# design.net
KiCad netlist of a schematic drawn in Altium Designer
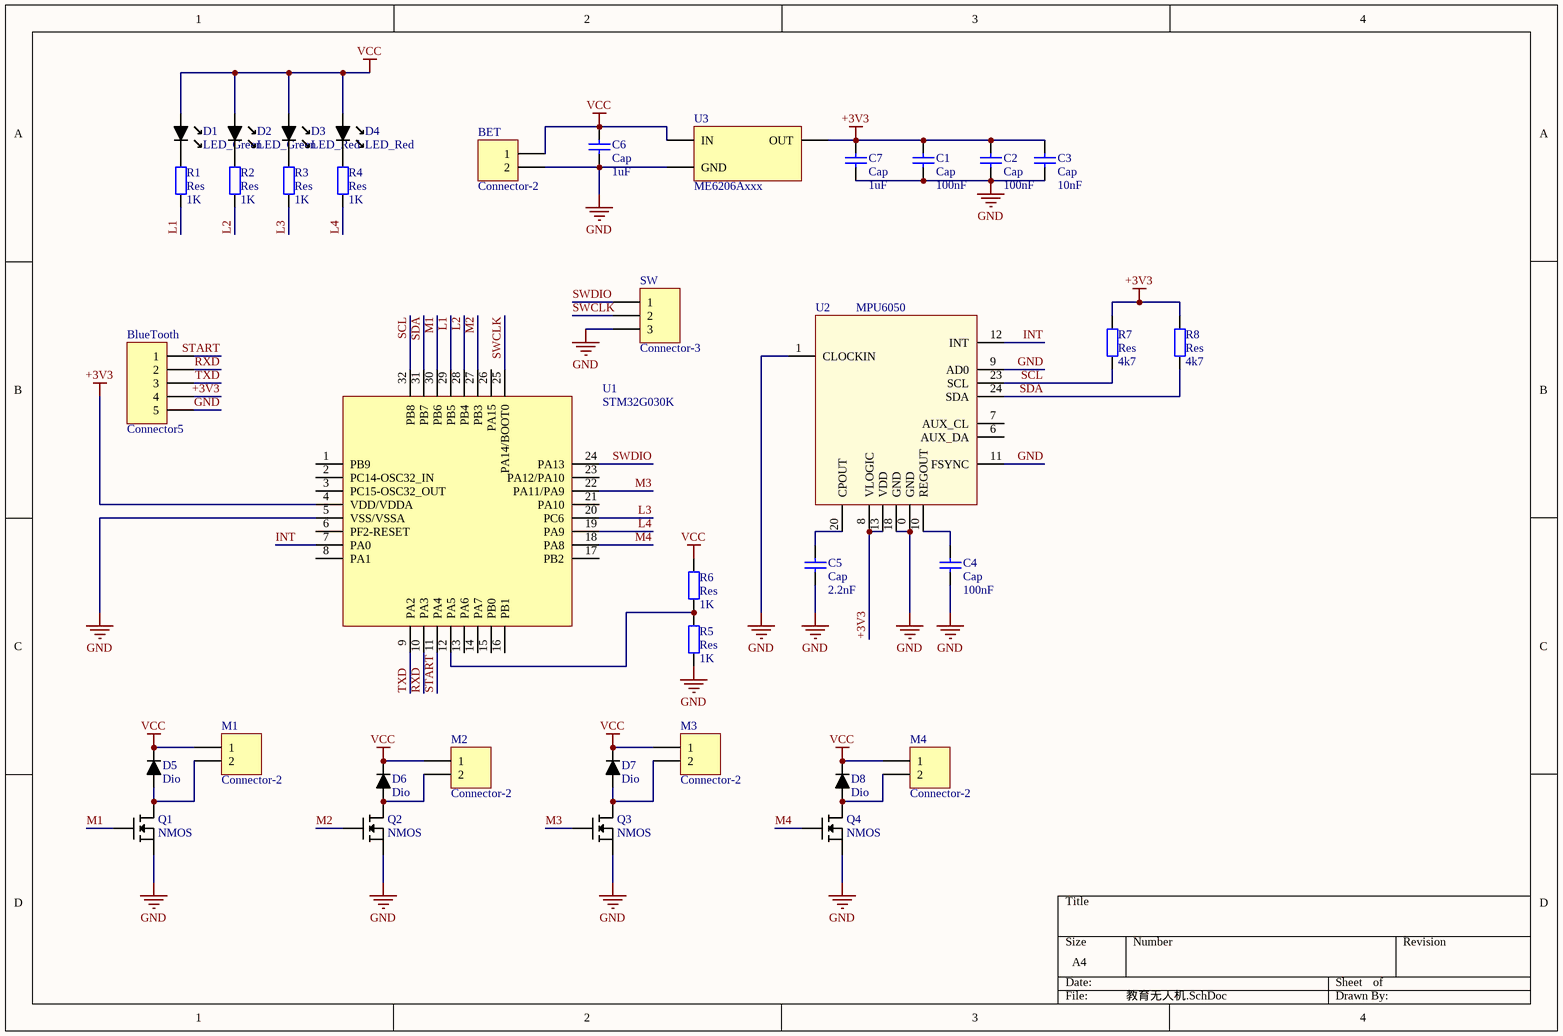
[diagram p0: 教育无人机.SchDoc]

(export (version "E")
  (design (tool "Eeschema 10.0.6"))
  (components
    (comp (ref "BET")
      (value "Connector-2")
      (footprint "XH2.54TH-2")
      (libsource (lib "") (part "Connector-2_1"))
    )
    (comp (ref "BlueTooth")
      (value "Connector5")
      (footprint "2.54th5")
      (libsource (lib "Connector") (part "Connector5"))
    )
    (comp (ref "C1")
      (value "Cap")
      (footprint "1206m")
      (description "Capacitor")
      (fields (field (name "ALTIUM_VALUE") "100nF") (field (name "PUBLISHER") "Altium Limited"))
      (libsource (lib "BasicDevice") (part "Cap"))
    )
    (comp (ref "C2")
      (value "Cap")
      (footprint "1206m")
      (description "Capacitor")
      (fields (field (name "ALTIUM_VALUE") "100nF") (field (name "PUBLISHER") "Altium Limited"))
      (libsource (lib "BasicDevice") (part "Cap"))
    )
    (comp (ref "C3")
      (value "Cap")
      (footprint "1206m")
      (description "Capacitor")
      (fields (field (name "ALTIUM_VALUE") "10nF") (field (name "PUBLISHER") "Altium Limited"))
      (libsource (lib "BasicDevice") (part "Cap"))
    )
    (comp (ref "C4")
      (value "Cap")
      (footprint "1206m")
      (description "Capacitor")
      (fields (field (name "ALTIUM_VALUE") "100nF") (field (name "PUBLISHER") "Altium Limited"))
      (libsource (lib "BasicDevice") (part "Cap"))
    )
    (comp (ref "C5")
      (value "Cap")
      (footprint "1206m")
      (description "Capacitor")
      (fields (field (name "ALTIUM_VALUE") "2.2nF") (field (name "PUBLISHER") "Altium Limited"))
      (libsource (lib "BasicDevice") (part "Cap"))
    )
    (comp (ref "C6")
      (value "Cap")
      (footprint "1206m")
      (description "Capacitor")
      (fields (field (name "ALTIUM_VALUE") "1uF") (field (name "PUBLISHER") "Altium Limited"))
      (libsource (lib "BasicDevice") (part "Cap"))
    )
    (comp (ref "C7")
      (value "Cap")
      (footprint "1206m")
      (description "Capacitor")
      (fields (field (name "ALTIUM_VALUE") "1uF") (field (name "PUBLISHER") "Altium Limited"))
      (libsource (lib "BasicDevice") (part "Cap"))
    )
    (comp (ref "D1") (value "LED_Green") (footprint "D0805M") (libsource (lib "BasicDevice") (part "LED")))
    (comp (ref "D2") (value "LED_Green") (footprint "D0805M") (libsource (lib "BasicDevice") (part "LED")))
    (comp (ref "D3") (value "LED_Red") (footprint "D0805M") (libsource (lib "BasicDevice") (part "LED")))
    (comp (ref "D4") (value "LED_Red") (footprint "D0805M") (libsource (lib "BasicDevice") (part "LED")))
    (comp (ref "D5") (value "Dio") (footprint "DO-214ACM") (libsource (lib "BasicDevice") (part "Dio")))
    (comp (ref "D6") (value "Dio") (footprint "DO-214ACM") (libsource (lib "BasicDevice") (part "Dio")))
    (comp (ref "D7") (value "Dio") (footprint "DO-214ACM") (libsource (lib "BasicDevice") (part "Dio")))
    (comp (ref "D8") (value "Dio") (footprint "DO-214ACM") (libsource (lib "BasicDevice") (part "Dio")))
    (comp (ref "M1")
      (value "Connector-2")
      (footprint "XH2.54TH-2")
      (libsource (lib "Connector") (part "Connector-2"))
    )
    (comp (ref "M2")
      (value "Connector-2")
      (footprint "XH2.54TH-2")
      (libsource (lib "Connector") (part "Connector-2"))
    )
    (comp (ref "M3")
      (value "Connector-2")
      (footprint "XH2.54TH-2")
      (libsource (lib "Connector") (part "Connector-2"))
    )
    (comp (ref "M4")
      (value "Connector-2")
      (footprint "XH2.54TH-2")
      (libsource (lib "Connector") (part "Connector-2"))
    )
    (comp (ref "Q1") (value "NMOS") (footprint "SOT23-3M") (libsource (lib "BasicDevice") (part "NMOS")))
    (comp (ref "Q2") (value "NMOS") (footprint "SOT23-3M") (libsource (lib "BasicDevice") (part "NMOS")))
    (comp (ref "Q3") (value "NMOS") (footprint "SOT23-3M") (libsource (lib "BasicDevice") (part "NMOS")))
    (comp (ref "Q4") (value "NMOS") (footprint "SOT23-3M") (libsource (lib "BasicDevice") (part "NMOS")))
    (comp (ref "R1")
      (value "Res")
      (footprint "1206M")
      (description "Resistor")
      (fields (field (name "ALTIUM_VALUE") "1K") (field (name "PUBLISHER") "Altium Limited"))
      (libsource (lib "BasicDevice") (part "Res"))
    )
    (comp (ref "R2")
      (value "Res")
      (footprint "1206M")
      (description "Resistor")
      (fields (field (name "ALTIUM_VALUE") "1K") (field (name "PUBLISHER") "Altium Limited"))
      (libsource (lib "BasicDevice") (part "Res"))
    )
    (comp (ref "R3")
      (value "Res")
      (footprint "1206M")
      (description "Resistor")
      (fields (field (name "ALTIUM_VALUE") "1K") (field (name "PUBLISHER") "Altium Limited"))
      (libsource (lib "BasicDevice") (part "Res"))
    )
    (comp (ref "R4")
      (value "Res")
      (footprint "1206M")
      (description "Resistor")
      (fields (field (name "ALTIUM_VALUE") "1K") (field (name "PUBLISHER") "Altium Limited"))
      (libsource (lib "BasicDevice") (part "Res"))
    )
    (comp (ref "R5")
      (value "Res")
      (footprint "LC-0805_R")
      (description "Resistor")
      (fields (field (name "ALTIUM_VALUE") "1K") (field (name "PUBLISHER") "Altium Limited"))
      (libsource (lib "BasicDevice") (part "Res"))
    )
    (comp (ref "R6")
      (value "Res")
      (footprint "LC-0805_R")
      (description "Resistor")
      (fields (field (name "ALTIUM_VALUE") "1K") (field (name "PUBLISHER") "Altium Limited"))
      (libsource (lib "BasicDevice") (part "Res"))
    )
    (comp (ref "R7")
      (value "Res")
      (footprint "LC-0805_R")
      (description "Resistor")
      (fields (field (name "ALTIUM_VALUE") "4k7") (field (name "PUBLISHER") "Altium Limited"))
      (libsource (lib "BasicDevice") (part "Res"))
    )
    (comp (ref "R8")
      (value "Res")
      (footprint "LC-0805_R")
      (description "Resistor")
      (fields (field (name "ALTIUM_VALUE") "4k7") (field (name "PUBLISHER") "Altium Limited"))
      (libsource (lib "BasicDevice") (part "Res"))
    )
    (comp (ref "SW")
      (value "Connector-3")
      (footprint "XH2.54TH-3")
      (libsource (lib "Connector") (part "Connector-3"))
    )
    (comp (ref "U1")
      (value "STM32G030K")
      (footprint "LQFP32M")
      (libsource (lib "STM32G0") (part "STM32G030K"))
    )
    (comp (ref "U2") (value "MPU6050") (footprint "QFN4*4-24M") (libsource (lib "MPU") (part "MPU6050")))
    (comp (ref "U3") (value "ME6206Axxx") (footprint "sot89m") (libsource (lib "ME") (part "ME6206Axxx")))
  )
  (nets
    (net (code "1") (name "+3V3") (class "Default")
      (node (ref "BlueTooth") (pin "4") (pinfunction "4_4") (pintype "power_in"))
      (node (ref "C1") (pin "1") (pinfunction "1_1") (pintype "passive"))
      (node (ref "C2") (pin "1") (pinfunction "1_1") (pintype "passive"))
      (node (ref "C3") (pin "1") (pinfunction "1_1") (pintype "passive"))
      (node (ref "C7") (pin "1") (pinfunction "1_1") (pintype "passive"))
      (node (ref "R7") (pin "2") (pinfunction "2_2") (pintype "passive"))
      (node (ref "R8") (pin "2") (pinfunction "2_2") (pintype "passive"))
      (node (ref "U1") (pin "4") (pinfunction "VDD/VDDA_4") (pintype "passive"))
      (node (ref "U2") (pin "13") (pinfunction "VDD_13") (pintype "passive"))
      (node (ref "U2") (pin "8") (pinfunction "VLOGIC_8") (pintype "passive"))
      (node (ref "U3") (pin "OUT") (pinfunction "OUT_OUT") (pintype "passive"))
    )
    (net (code "2") (name "/INT") (class "Default")
      (node (ref "U1") (pin "7") (pinfunction "PA0_7") (pintype "passive"))
      (node (ref "U2") (pin "12") (pinfunction "INT_12") (pintype "passive"))
    )
    (net (code "3") (name "/L1") (class "Default")
      (node (ref "R1") (pin "1") (pinfunction "1_1") (pintype "passive"))
      (node (ref "U1") (pin "29") (pinfunction "PB5_29") (pintype "passive"))
    )
    (net (code "4") (name "/L2") (class "Default")
      (node (ref "R2") (pin "1") (pinfunction "1_1") (pintype "passive"))
      (node (ref "U1") (pin "28") (pinfunction "PB4_28") (pintype "passive"))
    )
    (net (code "5") (name "/L3") (class "Default")
      (node (ref "R3") (pin "1") (pinfunction "1_1") (pintype "passive"))
      (node (ref "U1") (pin "20") (pinfunction "PC6_20") (pintype "passive"))
    )
    (net (code "6") (name "/L4") (class "Default")
      (node (ref "R4") (pin "1") (pinfunction "1_1") (pintype "passive"))
      (node (ref "U1") (pin "19") (pinfunction "PA9_19") (pintype "passive"))
    )
    (net (code "7") (name "/M1") (class "Default")
      (node (ref "Q1") (pin "G") (pinfunction "G_G") (pintype "passive"))
      (node (ref "U1") (pin "30") (pinfunction "PB6_30") (pintype "passive"))
    )
    (net (code "8") (name "/M2") (class "Default")
      (node (ref "Q2") (pin "G") (pinfunction "G_G") (pintype "passive"))
      (node (ref "U1") (pin "27") (pinfunction "PB3_27") (pintype "passive"))
    )
    (net (code "9") (name "/M3") (class "Default")
      (node (ref "Q3") (pin "G") (pinfunction "G_G") (pintype "passive"))
      (node (ref "U1") (pin "22") (pinfunction "PA11/PA9_22") (pintype "passive"))
    )
    (net (code "10") (name "/M4") (class "Default")
      (node (ref "Q4") (pin "G") (pinfunction "G_G") (pintype "passive"))
      (node (ref "U1") (pin "18") (pinfunction "PA8_18") (pintype "passive"))
    )
    (net (code "11") (name "/RXD") (class "Default")
      (node (ref "BlueTooth") (pin "2") (pinfunction "2_2") (pintype "power_in"))
      (node (ref "U1") (pin "10") (pinfunction "PA3_10") (pintype "passive"))
    )
    (net (code "12") (name "/SCL") (class "Default")
      (node (ref "R7") (pin "1") (pinfunction "1_1") (pintype "passive"))
      (node (ref "U1") (pin "32") (pinfunction "PB8_32") (pintype "passive"))
      (node (ref "U2") (pin "23") (pinfunction "SCL_23") (pintype "passive"))
    )
    (net (code "13") (name "/SDA") (class "Default")
      (node (ref "R8") (pin "1") (pinfunction "1_1") (pintype "passive"))
      (node (ref "U1") (pin "31") (pinfunction "PB7_31") (pintype "passive"))
      (node (ref "U2") (pin "24") (pinfunction "SDA_24") (pintype "passive"))
    )
    (net (code "14") (name "/START") (class "Default")
      (node (ref "BlueTooth") (pin "1") (pinfunction "1_1") (pintype "power_in"))
      (node (ref "U1") (pin "11") (pinfunction "PA4_11") (pintype "passive"))
    )
    (net (code "15") (name "/SWCLK") (class "Default")
      (node (ref "SW") (pin "2") (pinfunction "2_2") (pintype "passive"))
      (node (ref "U1") (pin "25") (pinfunction "PA14/BOOT0_25") (pintype "passive"))
    )
    (net (code "16") (name "/SWDIO") (class "Default")
      (node (ref "SW") (pin "1") (pinfunction "1_1") (pintype "passive"))
      (node (ref "U1") (pin "24") (pinfunction "PA13_24") (pintype "passive"))
    )
    (net (code "17") (name "/TXD") (class "Default")
      (node (ref "BlueTooth") (pin "3") (pinfunction "3_3") (pintype "power_in"))
      (node (ref "U1") (pin "9") (pinfunction "PA2_9") (pintype "passive"))
    )
    (net (code "18") (name "GND") (class "Default")
      (node (ref "BET") (pin "2") (pinfunction "2_2") (pintype "passive"))
      (node (ref "BlueTooth") (pin "5") (pinfunction "5_5") (pintype "power_in"))
      (node (ref "C1") (pin "2") (pinfunction "2_2") (pintype "passive"))
      (node (ref "C2") (pin "2") (pinfunction "2_2") (pintype "passive"))
      (node (ref "C3") (pin "2") (pinfunction "2_2") (pintype "passive"))
      (node (ref "C4") (pin "2") (pinfunction "2_2") (pintype "passive"))
      (node (ref "C5") (pin "2") (pinfunction "2_2") (pintype "passive"))
      (node (ref "C6") (pin "2") (pinfunction "2_2") (pintype "passive"))
      (node (ref "C7") (pin "2") (pinfunction "2_2") (pintype "passive"))
      (node (ref "Q1") (pin "S") (pinfunction "S_S") (pintype "passive"))
      (node (ref "Q2") (pin "S") (pinfunction "S_S") (pintype "passive"))
      (node (ref "Q3") (pin "S") (pinfunction "S_S") (pintype "passive"))
      (node (ref "Q4") (pin "S") (pinfunction "S_S") (pintype "passive"))
      (node (ref "R5") (pin "1") (pinfunction "1_1") (pintype "passive"))
      (node (ref "SW") (pin "3") (pinfunction "3_3") (pintype "passive"))
      (node (ref "U1") (pin "5") (pinfunction "VSS/VSSA_5") (pintype "passive"))
      (node (ref "U2") (pin "0") (pinfunction "GND_0") (pintype "passive"))
      (node (ref "U2") (pin "1") (pinfunction "CLOCKIN_1") (pintype "passive"))
      (node (ref "U2") (pin "11") (pinfunction "FSYNC_11") (pintype "passive"))
      (node (ref "U2") (pin "18") (pinfunction "GND_18") (pintype "passive"))
      (node (ref "U2") (pin "9") (pinfunction "AD0_9") (pintype "passive"))
      (node (ref "U3") (pin "GND") (pinfunction "GND_GND") (pintype "passive"))
    )
    (net (code "19") (name "Net-(D1-PadK)") (class "Default")
      (node (ref "D1") (pin "K") (pinfunction "K_K") (pintype "passive"))
      (node (ref "R1") (pin "2") (pinfunction "2_2") (pintype "passive"))
    )
    (net (code "20") (name "Net-(D2-PadK)") (class "Default")
      (node (ref "D2") (pin "K") (pinfunction "K_K") (pintype "passive"))
      (node (ref "R2") (pin "2") (pinfunction "2_2") (pintype "passive"))
    )
    (net (code "21") (name "Net-(D3-PadK)") (class "Default")
      (node (ref "D3") (pin "K") (pinfunction "K_K") (pintype "passive"))
      (node (ref "R3") (pin "2") (pinfunction "2_2") (pintype "passive"))
    )
    (net (code "22") (name "Net-(D4-PadK)") (class "Default")
      (node (ref "D4") (pin "K") (pinfunction "K_K") (pintype "passive"))
      (node (ref "R4") (pin "2") (pinfunction "2_2") (pintype "passive"))
    )
    (net (code "23") (name "Net-(D5-PadA)") (class "Default")
      (node (ref "D5") (pin "A") (pinfunction "A_A") (pintype "passive"))
      (node (ref "M1") (pin "2") (pinfunction "2_2") (pintype "passive"))
      (node (ref "Q1") (pin "D") (pinfunction "D_D") (pintype "passive"))
    )
    (net (code "24") (name "Net-(D6-PadA)") (class "Default")
      (node (ref "D6") (pin "A") (pinfunction "A_A") (pintype "passive"))
      (node (ref "M2") (pin "2") (pinfunction "2_2") (pintype "passive"))
      (node (ref "Q2") (pin "D") (pinfunction "D_D") (pintype "passive"))
    )
    (net (code "25") (name "Net-(D7-PadA)") (class "Default")
      (node (ref "D7") (pin "A") (pinfunction "A_A") (pintype "passive"))
      (node (ref "M3") (pin "2") (pinfunction "2_2") (pintype "passive"))
      (node (ref "Q3") (pin "D") (pinfunction "D_D") (pintype "passive"))
    )
    (net (code "26") (name "Net-(D8-PadA)") (class "Default")
      (node (ref "D8") (pin "A") (pinfunction "A_A") (pintype "passive"))
      (node (ref "M4") (pin "2") (pinfunction "2_2") (pintype "passive"))
      (node (ref "Q4") (pin "D") (pinfunction "D_D") (pintype "passive"))
    )
    (net (code "27") (name "Net-(U1-PA5)") (class "Default")
      (node (ref "R5") (pin "2") (pinfunction "2_2") (pintype "passive"))
      (node (ref "R6") (pin "1") (pinfunction "1_1") (pintype "passive"))
      (node (ref "U1") (pin "12") (pinfunction "PA5_12") (pintype "passive"))
    )
    (net (code "28") (name "Net-(U2-CPOUT)") (class "Default")
      (node (ref "C5") (pin "1") (pinfunction "1_1") (pintype "passive"))
      (node (ref "U2") (pin "20") (pinfunction "CPOUT_20") (pintype "passive"))
    )
    (net (code "29") (name "Net-(U2-REGOUT)") (class "Default")
      (node (ref "C4") (pin "1") (pinfunction "1_1") (pintype "passive"))
      (node (ref "U2") (pin "10") (pinfunction "REGOUT_10") (pintype "passive"))
    )
    (net (code "30") (name "VCC") (class "Default")
      (node (ref "BET") (pin "1") (pinfunction "1_1") (pintype "passive"))
      (node (ref "C6") (pin "1") (pinfunction "1_1") (pintype "passive"))
      (node (ref "D1") (pin "A") (pinfunction "A_A") (pintype "passive"))
      (node (ref "D2") (pin "A") (pinfunction "A_A") (pintype "passive"))
      (node (ref "D3") (pin "A") (pinfunction "A_A") (pintype "passive"))
      (node (ref "D4") (pin "A") (pinfunction "A_A") (pintype "passive"))
      (node (ref "D5") (pin "K") (pinfunction "K_K") (pintype "passive"))
      (node (ref "D6") (pin "K") (pinfunction "K_K") (pintype "passive"))
      (node (ref "D7") (pin "K") (pinfunction "K_K") (pintype "passive"))
      (node (ref "D8") (pin "K") (pinfunction "K_K") (pintype "passive"))
      (node (ref "M1") (pin "1") (pinfunction "1_1") (pintype "passive"))
      (node (ref "M2") (pin "1") (pinfunction "1_1") (pintype "passive"))
      (node (ref "M3") (pin "1") (pinfunction "1_1") (pintype "passive"))
      (node (ref "M4") (pin "1") (pinfunction "1_1") (pintype "passive"))
      (node (ref "R6") (pin "2") (pinfunction "2_2") (pintype "passive"))
      (node (ref "U3") (pin "IN") (pinfunction "IN_IN") (pintype "passive"))
    )
    (net (code "31") (name "unconnected-(U1-PA1-Pad8)") (class "Default")
      (node (ref "U1") (pin "8") (pinfunction "PA1_8") (pintype "passive"))
    )
    (net (code "32") (name "unconnected-(U1-PA6-Pad13)") (class "Default")
      (node (ref "U1") (pin "13") (pinfunction "PA6_13") (pintype "passive"))
    )
    (net (code "33") (name "unconnected-(U1-PA7-Pad14)") (class "Default")
      (node (ref "U1") (pin "14") (pinfunction "PA7_14") (pintype "passive"))
    )
    (net (code "34") (name "unconnected-(U1-PA10-Pad21)") (class "Default")
      (node (ref "U1") (pin "21") (pinfunction "PA10_21") (pintype "passive"))
    )
    (net (code "35") (name "unconnected-(U1-PA12{slash}PA10-Pad23)") (class "Default")
      (node (ref "U1") (pin "23") (pinfunction "PA12/PA10_23") (pintype "passive"))
    )
    (net (code "36") (name "unconnected-(U1-PA15-Pad26)") (class "Default")
      (node (ref "U1") (pin "26") (pinfunction "PA15_26") (pintype "passive"))
    )
    (net (code "37") (name "unconnected-(U1-PB0-Pad15)") (class "Default")
      (node (ref "U1") (pin "15") (pinfunction "PB0_15") (pintype "passive"))
    )
    (net (code "38") (name "unconnected-(U1-PB1-Pad16)") (class "Default")
      (node (ref "U1") (pin "16") (pinfunction "PB1_16") (pintype "passive"))
    )
    (net (code "39") (name "unconnected-(U1-PB2-Pad17)") (class "Default")
      (node (ref "U1") (pin "17") (pinfunction "PB2_17") (pintype "passive"))
    )
    (net (code "40") (name "unconnected-(U1-PB9-Pad1)") (class "Default")
      (node (ref "U1") (pin "1") (pinfunction "PB9_1") (pintype "passive"))
    )
    (net (code "41") (name "unconnected-(U1-PC14-OSC32_IN-Pad2)") (class "Default")
      (node (ref "U1") (pin "2") (pinfunction "PC14-OSC32_IN_2") (pintype "passive"))
    )
    (net (code "42") (name "unconnected-(U1-PC15-OSC32_OUT-Pad3)") (class "Default")
      (node (ref "U1") (pin "3") (pinfunction "PC15-OSC32_OUT_3") (pintype "passive"))
    )
    (net (code "43") (name "unconnected-(U1-PF2-RESET-Pad6)") (class "Default")
      (node (ref "U1") (pin "6") (pinfunction "PF2-RESET_6") (pintype "passive"))
    )
    (net (code "44") (name "unconnected-(U2-AUX_CL-Pad7)") (class "Default")
      (node (ref "U2") (pin "7") (pinfunction "AUX_CL_7") (pintype "passive"))
    )
    (net (code "45") (name "unconnected-(U2-AUX_DA-Pad6)") (class "Default")
      (node (ref "U2") (pin "6") (pinfunction "AUX_DA_6") (pintype "passive"))
    )
  )
)
